# YakupTrkn.net
KiCad netlist of a schematic drawn in Altium Designer
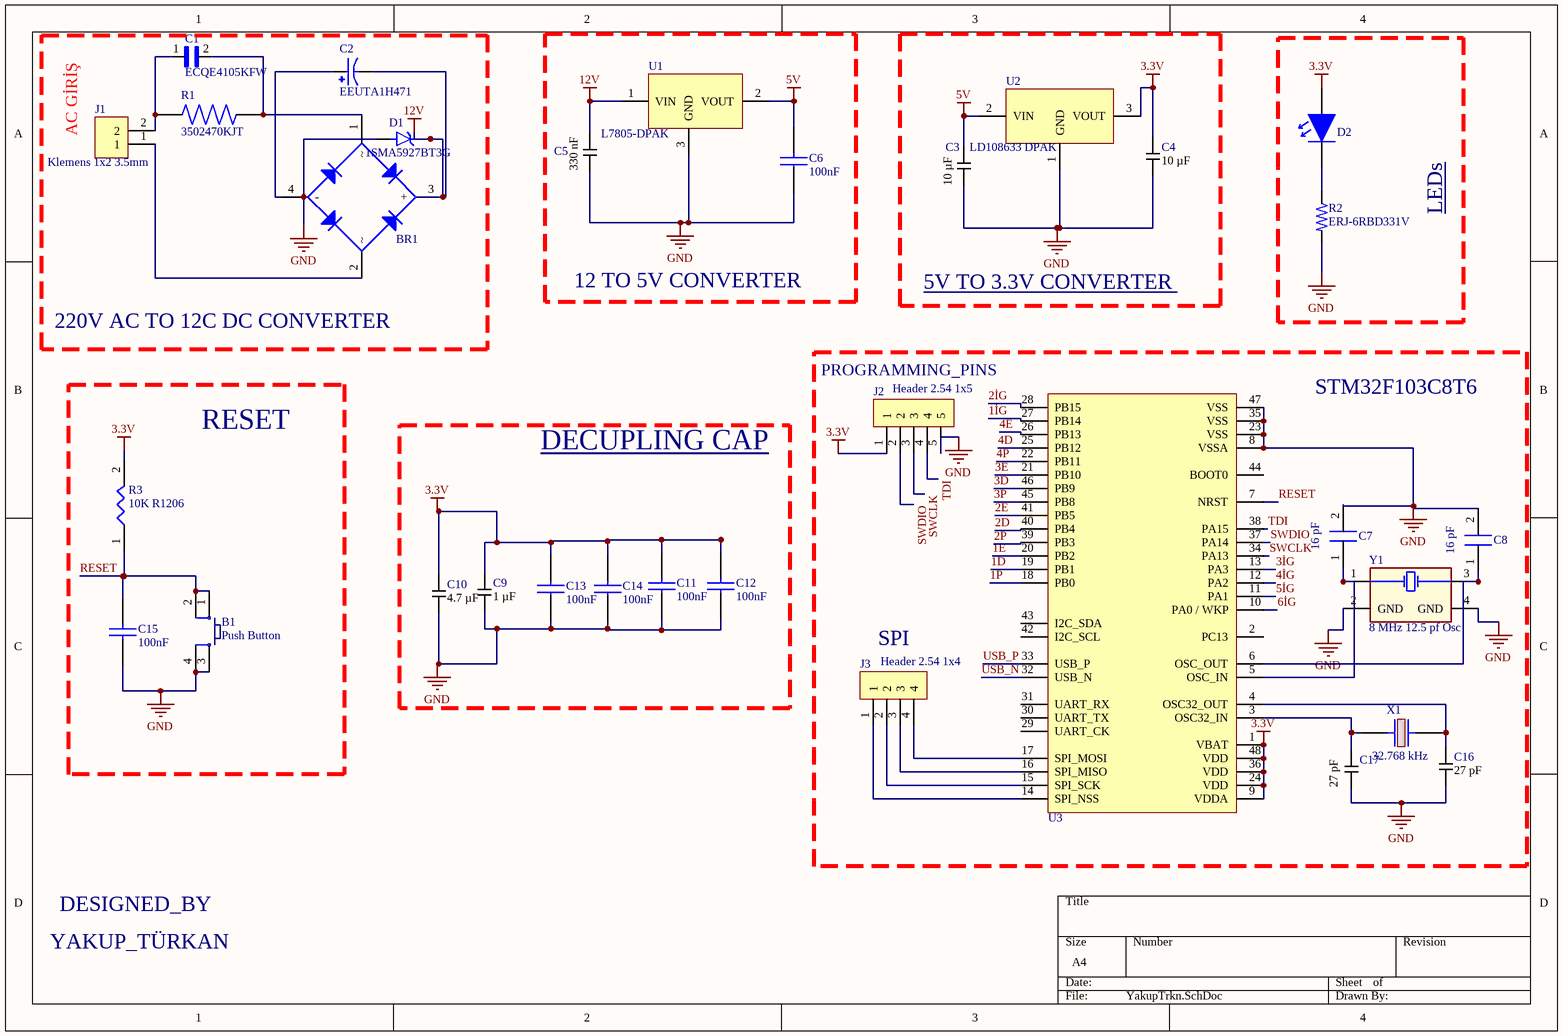
[diagram p0: YakupTrkn.SchDoc]

(export (version "E")
  (design (tool "Eeschema 10.0.6"))
  (components
    (comp (ref "B1")
      (value "Push Button")
      (footprint "PUSB BUTTON-SMD")
      (description "Smd Push Button")
      (libsource (lib "YakupTrkn") (part "Push Button"))
    )
    (comp (ref "BR1")
      (value "DB105STR")
      (footprint "DB105STR")
      (description "Bridge Diode AC-DC")
      (fields (field (name "MANUFACTURER") "Sangdest Microelectronics") (field (name "DESIGNED BY") "BERK"))
      (libsource (lib "YakupTrkn") (part "DB105STR"))
    )
    (comp (ref "C1")
      (value "ECQE4105KFW")
      (footprint "ECQE4105KFW:CAPRR1500W80L2600T850H2300")
      (fields (field (name "MF") "{'manufacturer': u'Panasonic'}"))
      (libsource (lib "YakupTrkn") (part "ECQE4105KFW"))
    )
    (comp (ref "C2")
      (value "EEUTA1H471")
      (footprint "EEU-TA1H471:CAPPRD750W80D1600H2000")
      (description "TA-A")
      (fields (field (name "MF") "{'manufacturer': u'Panasonic'}"))
      (libsource (lib "YakupTrkn") (part "EEUTA1H471"))
    )
    (comp (ref "C3")
      (value "CL21B106KPQNNNE")
      (footprint "SAMSUNG_CAP_0805_140")
      (description "CAP CER 10UF 10V X7R 0805")
      (fields (field (name "CAPACITANCE") "10 µF"))
      (libsource (lib "YakupTrkn") (part "CL21B106KPQNNNE"))
    )
    (comp (ref "C4")
      (value "CL21B106KPQNNNE")
      (footprint "SAMSUNG_CAP_0805_140")
      (description "CAP CER 10UF 10V X7R 0805")
      (fields (field (name "CAPACITANCE") "10 µF"))
      (libsource (lib "YakupTrkn") (part "CL21B106KPQNNNE"))
    )
    (comp (ref "C5")
      (value "CL21B334KOCNNNC")
      (footprint "SAMSUNG_CAP_0805_095")
      (description "CAP CER 0.33UF 16V X7R 0805")
      (fields (field (name "CAPACITANCE") "330 nF"))
      (libsource (lib "YakupTrkn") (part "CL21B334KOCNNNC"))
    )
    (comp (ref "C6")
      (value "C0603C104K5RACTU")
      (footprint "CAP_0603")
      (description "CAP CER 100nF %10 0603 SMD")
      (fields
        (field (name "MANUFACTURER") "KEMET")
        (field (name "TOLERANCE") "10%")
        (field (name "CAPACITANCE") "100nF")
        (field (name "DESIGNED BY") "BERK")
      )
      (libsource (lib "YakupTrkn") (part "CAP CER 100nF 0603"))
    )
    (comp (ref "C7") (value "16 pF") (footprint "C1206") (libsource (lib "YakupTrkn") (part "16 pF")))
    (comp (ref "C8") (value "16 pF") (footprint "C1206") (libsource (lib "YakupTrkn") (part "16 pF")))
    (comp (ref "C9")
      (value "CL21B105KBFNNNE")
      (footprint "SAMSUNG_CAP_0805_135")
      (description "CAP CER 1UF 50V X7R 0805")
      (fields (field (name "CAPACITANCE") "1 µF"))
      (libsource (lib "YakupTrkn") (part "CL21B105KBFNNNE"))
    )
    (comp (ref "C10")
      (value "*")
      (footprint "SAMSUNG_CAP_0805_095")
      (description "CAP CER 4.7UF 25V X5R 0805")
      (fields (field (name "CAPACITANCE") "4.7 µF"))
      (libsource (lib "*") (part "CL21A475KACLRNC"))
    )
    (comp (ref "C11")
      (value "C0603C104K5RACTU")
      (footprint "CAP_0603")
      (description "CAP CER 100nF %10 0603 SMD")
      (fields
        (field (name "MANUFACTURER") "KEMET")
        (field (name "TOLERANCE") "10%")
        (field (name "CAPACITANCE") "100nF")
        (field (name "DESIGNED BY") "BERK")
      )
      (libsource (lib "YakupTrkn") (part "CAP CER 100nF 0603"))
    )
    (comp (ref "C12")
      (value "C0603C104K5RACTU")
      (footprint "CAP_0603")
      (description "CAP CER 100nF %10 0603 SMD")
      (fields
        (field (name "MANUFACTURER") "KEMET")
        (field (name "TOLERANCE") "10%")
        (field (name "CAPACITANCE") "100nF")
        (field (name "DESIGNED BY") "BERK")
      )
      (libsource (lib "YakupTrkn") (part "CAP CER 100nF 0603"))
    )
    (comp (ref "C13")
      (value "C0603C104K5RACTU")
      (footprint "CAP_0603")
      (description "CAP CER 100nF %10 0603 SMD")
      (fields
        (field (name "MANUFACTURER") "KEMET")
        (field (name "TOLERANCE") "10%")
        (field (name "CAPACITANCE") "100nF")
        (field (name "DESIGNED BY") "BERK")
      )
      (libsource (lib "YakupTrkn") (part "CAP CER 100nF 0603"))
    )
    (comp (ref "C14")
      (value "C0603C104K5RACTU")
      (footprint "CAP_0603")
      (description "CAP CER 100nF %10 0603 SMD")
      (fields
        (field (name "MANUFACTURER") "KEMET")
        (field (name "TOLERANCE") "10%")
        (field (name "CAPACITANCE") "100nF")
        (field (name "DESIGNED BY") "BERK")
      )
      (libsource (lib "YakupTrkn") (part "CAP CER 100nF 0603"))
    )
    (comp (ref "C15")
      (value "C0603C104K5RACTU")
      (footprint "CAP_0603")
      (description "CAP CER 100nF %10 0603 SMD")
      (fields
        (field (name "MANUFACTURER") "KEMET")
        (field (name "TOLERANCE") "10%")
        (field (name "CAPACITANCE") "100nF")
        (field (name "DESIGNED BY") "BERK")
      )
      (libsource (lib "YakupTrkn") (part "CAP CER 100nF 0603"))
    )
    (comp (ref "C16")
      (value "CL21C270JBANNNC")
      (footprint "SAMSUNG_CAP_0805_075")
      (description "CAP CER 27PF 50V C0G/NP0 0805")
      (fields (field (name "CAPACITANCE") "27 pF"))
      (libsource (lib "YakupTrkn") (part "CL21C270JBANNNC"))
    )
    (comp (ref "C17")
      (value "CL21C270JBANNNC")
      (footprint "SAMSUNG_CAP_0805_075")
      (description "CAP CER 27PF 50V C0G/NP0 0805")
      (fields (field (name "CAPACITANCE") "27 pF"))
      (libsource (lib "YakupTrkn") (part "CL21C270JBANNNC"))
    )
    (comp (ref "D1")
      (value "1SMA5927BT3G")
      (footprint "1SMA5927BT3G:DIOM5226X220N")
      (fields (field (name "MF") "{'manufacturer': u'ON Semiconductor'}"))
      (libsource (lib "YakupTrkn") (part "1SMA5927BT3G"))
    )
    (comp (ref "D2")
      (value "LH R974-LP-1")
      (footprint "LED_RED_0805")
      (description "LED Uni-Color Hyper Red 660nm 2-Pin Chip 0805(2012Metric) T/R")
      (fields (field (name "MANUFACTURER") "Osram Opto") (field (name "DESIGNED BY") "BERK"))
      (libsource (lib "YakupTrkn") (part "LED RED 0805"))
    )
    (comp (ref "J1")
      (value "Klemens 1x2 3.5mm")
      (footprint "Klemens 1x2 - 3.5mm")
      (libsource (lib "YakupTrkn") (part "Klemens 1x2 3.5mm"))
    )
    (comp (ref "J2")
      (value "Header 2.54 1x5")
      (footprint "Header 2.54 1x5")
      (libsource (lib "YakupTrkn") (part "Header 2.54 1x5"))
    )
    (comp (ref "J3")
      (value "Header 2.54 1x4")
      (footprint "Header 2.54 1x4")
      (libsource (lib "YakupTrkn") (part "Header 2.54 1x4"))
    )
    (comp (ref "R1")
      (value "3502470KJT")
      (footprint "3502470KJT:RESC5025X120N")
      (fields (field (name "MF") "{'manufacturer': u'TE Connectivity'}"))
      (libsource (lib "YakupTrkn") (part "3502470KJT"))
    )
    (comp (ref "R2")
      (value "ERJ-6RBD331V")
      (footprint "ERJ-6RBD331V:RESC2012X70")
      (description "Thick Film Chip Res,0805, 0.5% Precision 330ohm, 5")
      (fields (field (name "MF") "{'manufacturer': u'Panasonic'}"))
      (libsource (lib "YakupTrkn") (part "ERJ-6RBD331V"))
    )
    (comp (ref "R3")
      (value "10K R1206")
      (footprint "R1206 Resıstor")
      (libsource (lib "YakupTrkn") (part "10K R1206"))
    )
    (comp (ref "U1")
      (value "L7805-DPAK")
      (footprint "DPAK228P972X230-3N")
      (description "L7805 5V REGULATOR. SMD PAKET")
      (libsource (lib "YakupTrkn") (part "L7805-DPAK"))
    )
    (comp (ref "U2")
      (value "LD108633 DPAK")
      (footprint "DPAK228P972X230-3N")
      (description "LD1086 3.3V REGULATOR")
      (libsource (lib "YakupTrkn") (part "LD108633 DPAK"))
    )
    (comp (ref "U3")
      (value "STM32F103C6T6A")
      (footprint "LQFP-48")
      (description "MCU 32-bit STM32F ARM Cortex M3 RISC 32KB Flash 2.5V/3.3V 48-Pin LQFP Tray")
      (fields (field (name "MANUFACTURER") "STMicroelectronics") (field (name "DESIGNED BY") "BERK"))
      (libsource (lib "YakupTrkn") (part "STM32F103C6T6A"))
    )
    (comp (ref "X1")
      (value "ABS05-32.768KHZ-T")
      (footprint "ABS05")
      (description "Crystal, 32.768 kHz, SMD, 1.6mm x 1mm, 12.5 pF, 20 ppm, ABS05 Series")
      (fields
        (field (name "MANUFACTURER") "Abracon")
        (field (name "TOLERANCE") "20ppm")
        (field (name "OPERATING FREQUENCY") "32.768 kHz")
        (field (name "DESIGNED BY") "BERK")
      )
      (libsource (lib "YakupTrkn") (part "CRYSTAL 32768kHZ_1"))
    )
    (comp (ref "Y1")
      (value "8 MHz 12.5 pf Osc")
      (footprint "8 MHZ Osc.")
      (libsource (lib "YakupTrkn") (part "8 MHz 12.5 pf Osc"))
    )
  )
  (nets
    (net (code "1") (name "/1D") (class "Default")
      (node (ref "U3") (pin "19") (pinfunction "PB1_19") (pintype "passive"))
    )
    (net (code "2") (name "/1E") (class "Default")
      (node (ref "U3") (pin "20") (pinfunction "PB2_20") (pintype "passive"))
    )
    (net (code "3") (name "/1P") (class "Default")
      (node (ref "U3") (pin "18") (pinfunction "PB0_18") (pintype "passive"))
    )
    (net (code "4") (name "/1İG") (class "Default")
      (node (ref "U3") (pin "27") (pinfunction "PB14_27") (pintype "passive"))
    )
    (net (code "5") (name "/2D") (class "Default")
      (node (ref "U3") (pin "40") (pinfunction "PB4_40") (pintype "passive"))
    )
    (net (code "6") (name "/2E") (class "Default")
      (node (ref "U3") (pin "41") (pinfunction "PB5_41") (pintype "passive"))
    )
    (net (code "7") (name "/2P") (class "Default")
      (node (ref "U3") (pin "39") (pinfunction "PB3_39") (pintype "passive"))
    )
    (net (code "8") (name "/2İG") (class "Default")
      (node (ref "U3") (pin "28") (pinfunction "PB15_28") (pintype "passive"))
    )
    (net (code "9") (name "/3D") (class "Default")
      (node (ref "U3") (pin "46") (pinfunction "PB9_46") (pintype "passive"))
    )
    (net (code "10") (name "/3E") (class "Default")
      (node (ref "U3") (pin "21") (pinfunction "PB10_21") (pintype "passive"))
    )
    (net (code "11") (name "/3P") (class "Default")
      (node (ref "U3") (pin "45") (pinfunction "PB8_45") (pintype "passive"))
    )
    (net (code "12") (name "/3İG") (class "Default")
      (node (ref "U3") (pin "13") (pinfunction "PA3_13") (pintype "passive"))
    )
    (net (code "13") (name "/4D") (class "Default")
      (node (ref "U3") (pin "25") (pinfunction "PB12_25") (pintype "passive"))
    )
    (net (code "14") (name "/4E") (class "Default")
      (node (ref "U3") (pin "26") (pinfunction "PB13_26") (pintype "passive"))
    )
    (net (code "15") (name "/4P") (class "Default")
      (node (ref "U3") (pin "22") (pinfunction "PB11_22") (pintype "passive"))
    )
    (net (code "16") (name "/4İG") (class "Default")
      (node (ref "U3") (pin "12") (pinfunction "PA2_12") (pintype "passive"))
    )
    (net (code "17") (name "/5İG") (class "Default")
      (node (ref "U3") (pin "11") (pinfunction "PA1_11") (pintype "passive"))
    )
    (net (code "18") (name "/6İG") (class "Default")
      (node (ref "U3") (pin "10") (pinfunction "PA0_/_WKP_10") (pintype "passive"))
    )
    (net (code "19") (name "/RESET") (class "Default")
      (node (ref "B1") (pin "1") (pinfunction "1_1") (pintype "passive"))
      (node (ref "B1") (pin "2") (pinfunction "2_2") (pintype "passive"))
      (node (ref "C15") (pin "2") (pinfunction "2_2") (pintype "passive"))
      (node (ref "R3") (pin "1") (pinfunction "1_1") (pintype "passive"))
      (node (ref "U3") (pin "7") (pinfunction "NRST_7") (pintype "passive"))
    )
    (net (code "20") (name "/SWCLK") (class "Default")
      (node (ref "J2") (pin "3") (pinfunction "3_3") (pintype "passive"))
      (node (ref "U3") (pin "34") (pinfunction "PA13_34") (pintype "passive"))
    )
    (net (code "21") (name "/SWDIO") (class "Default")
      (node (ref "J2") (pin "2") (pinfunction "2_2") (pintype "passive"))
      (node (ref "U3") (pin "37") (pinfunction "PA14_37") (pintype "passive"))
    )
    (net (code "22") (name "/TDI") (class "Default")
      (node (ref "J2") (pin "4") (pinfunction "4_4") (pintype "passive"))
      (node (ref "U3") (pin "38") (pinfunction "PA15_38") (pintype "passive"))
    )
    (net (code "23") (name "/USB_N") (class "Default")
      (node (ref "U3") (pin "32") (pinfunction "USB_N_32") (pintype "passive"))
    )
    (net (code "24") (name "/USB_P") (class "Default")
      (node (ref "U3") (pin "33") (pinfunction "USB_P_33") (pintype "passive"))
    )
    (net (code "25") (name "3.3V") (class "Default")
      (node (ref "C10") (pin "2") (pinfunction "2_2") (pintype "passive"))
      (node (ref "C11") (pin "2") (pinfunction "2_2") (pintype "passive"))
      (node (ref "C12") (pin "2") (pinfunction "2_2") (pintype "passive"))
      (node (ref "C13") (pin "2") (pinfunction "2_2") (pintype "passive"))
      (node (ref "C14") (pin "2") (pinfunction "2_2") (pintype "passive"))
      (node (ref "C4") (pin "1") (pinfunction "1_1") (pintype "passive"))
      (node (ref "C9") (pin "2") (pinfunction "2_2") (pintype "passive"))
      (node (ref "D2") (pin "2") (pinfunction "2_2") (pintype "power_in"))
      (node (ref "J2") (pin "1") (pinfunction "1_1") (pintype "passive"))
      (node (ref "R3") (pin "2") (pinfunction "2_2") (pintype "passive"))
      (node (ref "U2") (pin "3") (pinfunction "VOUT_3") (pintype "passive"))
      (node (ref "U3") (pin "1") (pinfunction "VBAT_1") (pintype "passive"))
      (node (ref "U3") (pin "24") (pinfunction "VDD_24") (pintype "passive"))
      (node (ref "U3") (pin "36") (pinfunction "VDD_36") (pintype "passive"))
      (node (ref "U3") (pin "48") (pinfunction "VDD_48") (pintype "passive"))
      (node (ref "U3") (pin "9") (pinfunction "VDDA_9") (pintype "passive"))
    )
    (net (code "26") (name "5V") (class "Default")
      (node (ref "C3") (pin "2") (pinfunction "2_2") (pintype "passive"))
      (node (ref "C6") (pin "2") (pinfunction "2_2") (pintype "passive"))
      (node (ref "U1") (pin "2") (pinfunction "VOUT_2") (pintype "passive"))
      (node (ref "U2") (pin "2") (pinfunction "VIN_2") (pintype "passive"))
    )
    (net (code "27") (name "12V") (class "Default")
      (node (ref "BR1") (pin "3") (pinfunction "+_3") (pintype "passive"))
      (node (ref "C2") (pin "N") (pinfunction "N_N") (pintype "passive"))
      (node (ref "C5") (pin "2") (pinfunction "2_2") (pintype "passive"))
      (node (ref "D1") (pin "C") (pinfunction "C_C") (pintype "passive"))
      (node (ref "U1") (pin "1") (pinfunction "VIN_1") (pintype "passive"))
    )
    (net (code "28") (name "GND") (class "Default")
      (node (ref "B1") (pin "3") (pinfunction "3_3") (pintype "passive"))
      (node (ref "B1") (pin "4") (pinfunction "4_4") (pintype "passive"))
      (node (ref "C10") (pin "1") (pinfunction "1_1") (pintype "passive"))
      (node (ref "C11") (pin "1") (pinfunction "1_1") (pintype "passive"))
      (node (ref "C12") (pin "1") (pinfunction "1_1") (pintype "passive"))
      (node (ref "C13") (pin "1") (pinfunction "1_1") (pintype "passive"))
      (node (ref "C14") (pin "1") (pinfunction "1_1") (pintype "passive"))
      (node (ref "C15") (pin "1") (pinfunction "1_1") (pintype "passive"))
      (node (ref "C16") (pin "1") (pinfunction "1_1") (pintype "passive"))
      (node (ref "C17") (pin "2") (pinfunction "2_2") (pintype "passive"))
      (node (ref "C3") (pin "1") (pinfunction "1_1") (pintype "passive"))
      (node (ref "C4") (pin "2") (pinfunction "2_2") (pintype "passive"))
      (node (ref "C5") (pin "1") (pinfunction "1_1") (pintype "passive"))
      (node (ref "C6") (pin "1") (pinfunction "1_1") (pintype "passive"))
      (node (ref "C7") (pin "2") (pinfunction "2_2") (pintype "passive"))
      (node (ref "C8") (pin "2") (pinfunction "2_2") (pintype "passive"))
      (node (ref "C9") (pin "1") (pinfunction "1_1") (pintype "passive"))
      (node (ref "D1") (pin "A") (pinfunction "A_A") (pintype "passive"))
      (node (ref "J2") (pin "5") (pinfunction "5_5") (pintype "passive"))
      (node (ref "R2") (pin "2") (pinfunction "2_2") (pintype "passive"))
      (node (ref "U1") (pin "3") (pinfunction "GND_3") (pintype "passive"))
      (node (ref "U2") (pin "1") (pinfunction "GND_1") (pintype "passive"))
      (node (ref "U3") (pin "23") (pinfunction "VSS_23") (pintype "passive"))
      (node (ref "U3") (pin "35") (pinfunction "VSS_35") (pintype "passive"))
      (node (ref "U3") (pin "47") (pinfunction "VSS_47") (pintype "passive"))
      (node (ref "U3") (pin "8") (pinfunction "VSSA_8") (pintype "passive"))
      (node (ref "Y1") (pin "2") (pinfunction "GND_2") (pintype "power_in"))
      (node (ref "Y1") (pin "4") (pinfunction "GND_4") (pintype "passive"))
    )
    (net (code "29") (name "Net-(BR1--)") (class "Default")
      (node (ref "BR1") (pin "4") (pinfunction "-_4") (pintype "passive"))
      (node (ref "C2") (pin "P") (pinfunction "P_P") (pintype "passive"))
    )
    (net (code "30") (name "Net-(BR1-~-Pad1)") (class "Default")
      (node (ref "BR1") (pin "1") (pinfunction "~_1") (pintype "passive"))
      (node (ref "C1") (pin "2") (pinfunction "2_2") (pintype "passive"))
      (node (ref "R1") (pin "2") (pinfunction "2_2") (pintype "passive"))
    )
    (net (code "31") (name "Net-(BR1-~-Pad2)") (class "Default")
      (node (ref "BR1") (pin "2") (pinfunction "~_2") (pintype "passive"))
      (node (ref "J1") (pin "1") (pinfunction "1_1") (pintype "passive"))
    )
    (net (code "32") (name "Net-(C1-Pad1)") (class "Default")
      (node (ref "C1") (pin "1") (pinfunction "1_1") (pintype "passive"))
      (node (ref "J1") (pin "2") (pinfunction "2_2") (pintype "passive"))
      (node (ref "R1") (pin "1") (pinfunction "1_1") (pintype "passive"))
    )
    (net (code "33") (name "Net-(D2-Pad1)") (class "Default")
      (node (ref "D2") (pin "1") (pinfunction "1_1") (pintype "power_in"))
      (node (ref "R2") (pin "1") (pinfunction "1_1") (pintype "passive"))
    )
    (net (code "34") (name "Net-(U3-OSC32_IN)") (class "Default")
      (node (ref "C17") (pin "1") (pinfunction "1_1") (pintype "passive"))
      (node (ref "U3") (pin "3") (pinfunction "OSC32_IN_3") (pintype "passive"))
      (node (ref "X1") (pin "1") (pinfunction "1_1") (pintype "passive"))
    )
    (net (code "35") (name "Net-(U3-OSC32_OUT)") (class "Default")
      (node (ref "C16") (pin "2") (pinfunction "2_2") (pintype "passive"))
      (node (ref "U3") (pin "4") (pinfunction "OSC32_OUT_4") (pintype "passive"))
      (node (ref "X1") (pin "2") (pinfunction "2_2") (pintype "passive"))
    )
    (net (code "36") (name "Net-(U3-OSC_IN)") (class "Default")
      (node (ref "C7") (pin "1") (pinfunction "1_1") (pintype "passive"))
      (node (ref "U3") (pin "5") (pinfunction "OSC_IN_5") (pintype "passive"))
      (node (ref "Y1") (pin "1") (pintype "power_in"))
    )
    (net (code "37") (name "Net-(U3-OSC_OUT)") (class "Default")
      (node (ref "C8") (pin "1") (pinfunction "1_1") (pintype "passive"))
      (node (ref "U3") (pin "6") (pinfunction "OSC_OUT_6") (pintype "passive"))
      (node (ref "Y1") (pin "3") (pintype "passive"))
    )
    (net (code "38") (name "Net-(U3-SPI_MISO)") (class "Default")
      (node (ref "J3") (pin "3") (pinfunction "3_3") (pintype "passive"))
      (node (ref "U3") (pin "16") (pinfunction "SPI_MISO_16") (pintype "passive"))
    )
    (net (code "39") (name "Net-(U3-SPI_MOSI)") (class "Default")
      (node (ref "J3") (pin "4") (pinfunction "4_4") (pintype "passive"))
      (node (ref "U3") (pin "17") (pinfunction "SPI_MOSI_17") (pintype "passive"))
    )
    (net (code "40") (name "Net-(U3-SPI_NSS)") (class "Default")
      (node (ref "J3") (pin "1") (pinfunction "1_1") (pintype "passive"))
      (node (ref "U3") (pin "14") (pinfunction "SPI_NSS_14") (pintype "passive"))
    )
    (net (code "41") (name "Net-(U3-SPI_SCK)") (class "Default")
      (node (ref "J3") (pin "2") (pinfunction "2_2") (pintype "passive"))
      (node (ref "U3") (pin "15") (pinfunction "SPI_SCK_15") (pintype "passive"))
    )
    (net (code "42") (name "unconnected-(U3-BOOT0-Pad44)") (class "Default")
      (node (ref "U3") (pin "44") (pinfunction "BOOT0_44") (pintype "passive"))
    )
    (net (code "43") (name "unconnected-(U3-I2C_SCL-Pad42)") (class "Default")
      (node (ref "U3") (pin "42") (pinfunction "I2C_SCL_42") (pintype "passive"))
    )
    (net (code "44") (name "unconnected-(U3-I2C_SDA-Pad43)") (class "Default")
      (node (ref "U3") (pin "43") (pinfunction "I2C_SDA_43") (pintype "passive"))
    )
    (net (code "45") (name "unconnected-(U3-PC13-Pad2)") (class "Default")
      (node (ref "U3") (pin "2") (pinfunction "PC13_2") (pintype "passive"))
    )
    (net (code "46") (name "unconnected-(U3-UART_CK-Pad29)") (class "Default")
      (node (ref "U3") (pin "29") (pinfunction "UART_CK_29") (pintype "passive"))
    )
    (net (code "47") (name "unconnected-(U3-UART_RX-Pad31)") (class "Default")
      (node (ref "U3") (pin "31") (pinfunction "UART_RX_31") (pintype "passive"))
    )
    (net (code "48") (name "unconnected-(U3-UART_TX-Pad30)") (class "Default")
      (node (ref "U3") (pin "30") (pinfunction "UART_TX_30") (pintype "passive"))
    )
  )
)
